# 08_B2B.net
KiCad netlist of a schematic drawn in Altium Designer
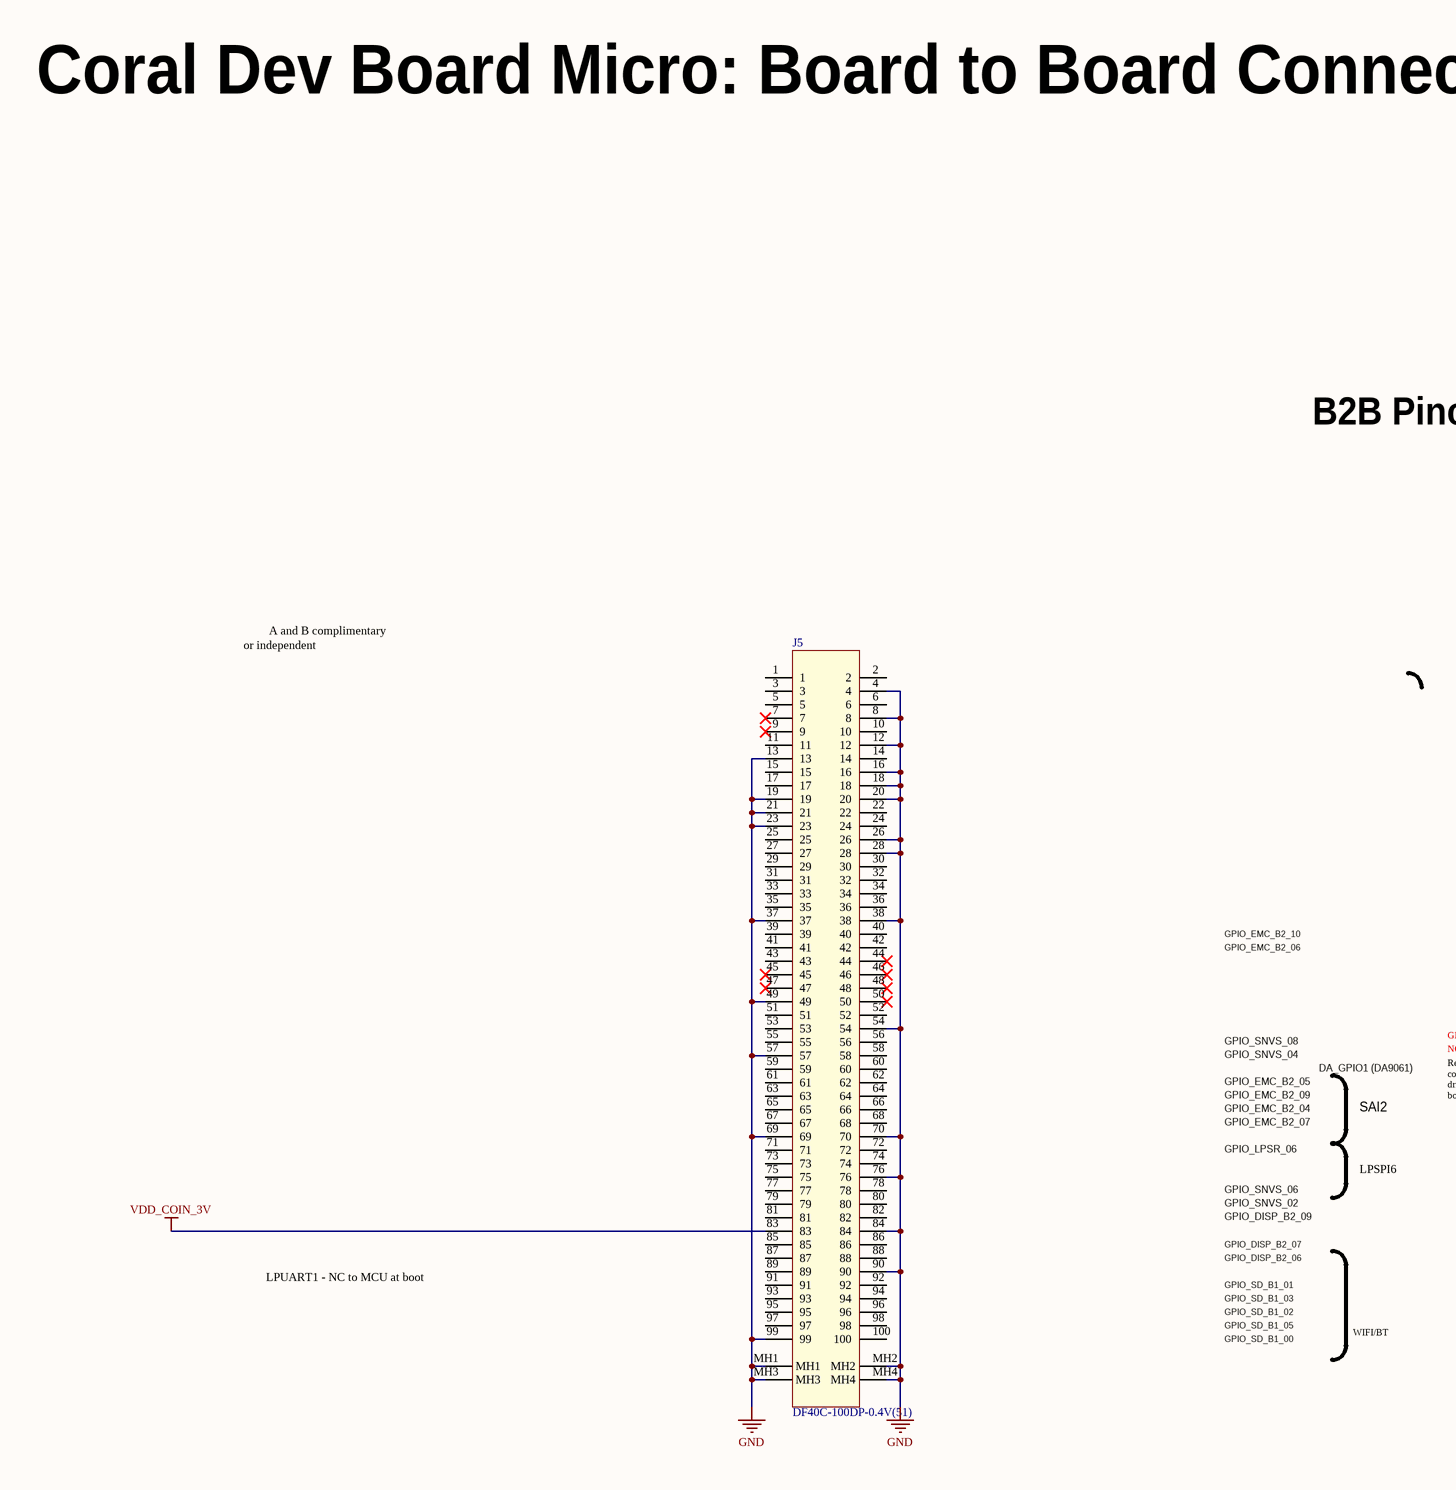
[diagram p0: 08 B2B.SchDoc, left]
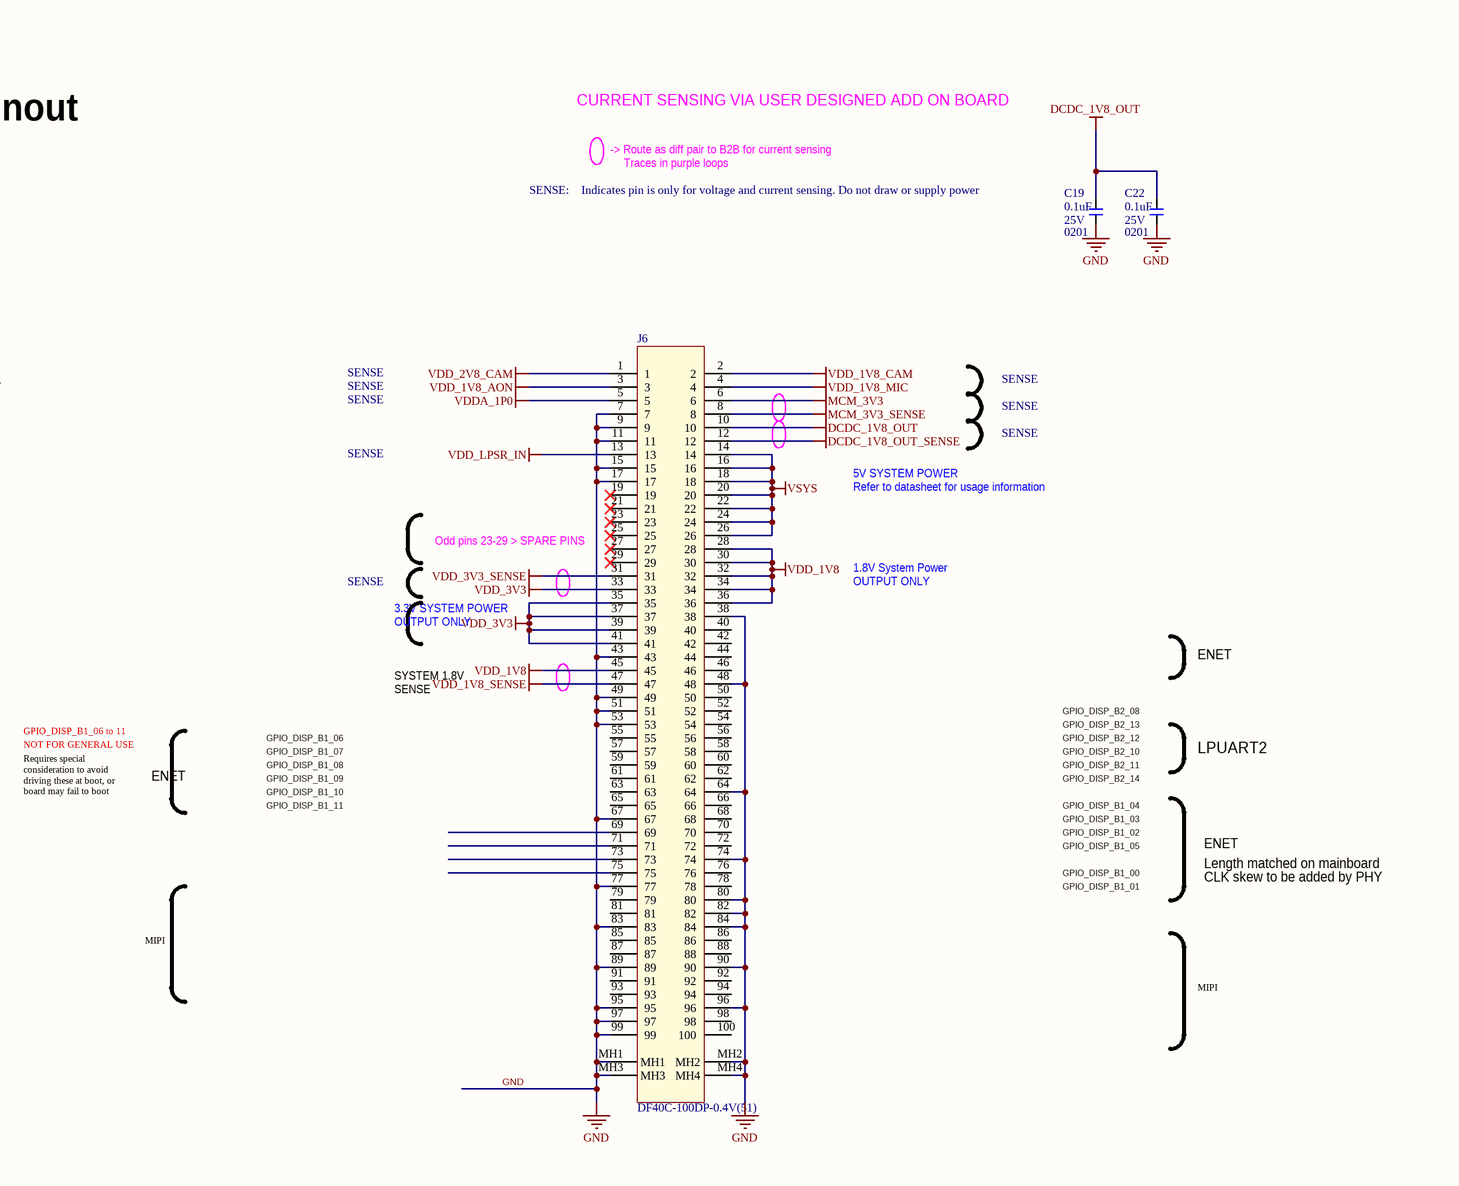
[diagram p1: 08 B2B.SchDoc, right]

(export (version "E")
  (design (tool "Eeschema 10.0.6"))
  (components
    (comp (ref "C19")
      (value "0.1uF")
      (footprint "C0201Y")
      (description "CAP, CER, X5R, 0.1uF, 25V, 20%, 0201, 0.33mm T")
      (fields
        (field (name "MFG") "MURATA")
        (field (name "PACKAGE") "0201")
        (field (name "VOLTAGE") "25V")
        (field (name "TOLERANCE") "20%")
      )
      (libsource (lib "AltiumReleaseLibDB") (part "__Template_Cap"))
    )
    (comp (ref "C22")
      (value "0.1uF")
      (footprint "C0201Y")
      (description "CAP, CER, X5R, 0.1uF, 25V, 20%, 0201, 0.33mm T")
      (fields
        (field (name "MFG") "MURATA")
        (field (name "PACKAGE") "0201")
        (field (name "VOLTAGE") "25V")
        (field (name "TOLERANCE") "20%")
      )
      (libsource (lib "AltiumReleaseLibDB") (part "__Template_Cap"))
    )
    (comp (ref "J5")
      (value "~")
      (footprint "HIROSE_DF40C-100DP-0.4V(51)")
      (description "CONN, HDR, VERT, 2x50, 0.4MM P, 1.14MM H, GOLD, SMD")
      (fields (field (name "MFG") "Hirose Electric Co Ltd") (field (name "MFG P/N") "DF40C-100DP-0.4V(51)"))
      (libsource (lib "AltiumReleaseLibDB") (part "__Template_Connector_2X50_4MH"))
    )
    (comp (ref "J6")
      (value "~")
      (footprint "HIROSE_DF40C-100DP-0.4V(51)")
      (description "CONN, HDR, VERT, 2x50, 0.4MM P, 1.14MM H, GOLD, SMD")
      (fields (field (name "MFG") "Hirose Electric Co Ltd") (field (name "MFG P/N") "DF40C-100DP-0.4V(51)"))
      (libsource (lib "AltiumReleaseLibDB") (part "__Template_Connector_2X50_4MH"))
    )
  )
  (nets
    (net (code "1") (name "DCDC_1V8_OUT") (class "Default")
      (node (ref "C19") (pin "1") (pintype "passive"))
      (node (ref "C22") (pin "1") (pintype "passive"))
      (node (ref "J6") (pin "10") (pinfunction "10_10") (pintype "passive"))
    )
    (net (code "2") (name "DCDC_1V8_OUT_SENSE") (class "Default")
      (node (ref "J6") (pin "12") (pinfunction "12_12") (pintype "passive"))
    )
    (net (code "3") (name "GND") (class "Default")
      (node (ref "C19") (pin "2") (pintype "passive"))
      (node (ref "C22") (pin "2") (pintype "passive"))
      (node (ref "J5") (pin "12") (pinfunction "12_12") (pintype "passive"))
      (node (ref "J5") (pin "13") (pinfunction "13_13") (pintype "passive"))
      (node (ref "J5") (pin "16") (pinfunction "16_16") (pintype "passive"))
      (node (ref "J5") (pin "18") (pinfunction "18_18") (pintype "passive"))
      (node (ref "J5") (pin "19") (pinfunction "19_19") (pintype "passive"))
      (node (ref "J5") (pin "20") (pinfunction "20_20") (pintype "passive"))
      (node (ref "J5") (pin "21") (pinfunction "21_21") (pintype "passive"))
      (node (ref "J5") (pin "23") (pinfunction "23_23") (pintype "passive"))
      (node (ref "J5") (pin "26") (pinfunction "26_26") (pintype "passive"))
      (node (ref "J5") (pin "28") (pinfunction "28_28") (pintype "passive"))
      (node (ref "J5") (pin "37") (pinfunction "37_37") (pintype "passive"))
      (node (ref "J5") (pin "38") (pinfunction "38_38") (pintype "passive"))
      (node (ref "J5") (pin "4") (pinfunction "4_4") (pintype "passive"))
      (node (ref "J5") (pin "49") (pinfunction "49_49") (pintype "passive"))
      (node (ref "J5") (pin "54") (pinfunction "54_54") (pintype "passive"))
      (node (ref "J5") (pin "57") (pinfunction "57_57") (pintype "passive"))
      (node (ref "J5") (pin "69") (pinfunction "69_69") (pintype "passive"))
      (node (ref "J5") (pin "70") (pinfunction "70_70") (pintype "passive"))
      (node (ref "J5") (pin "76") (pinfunction "76_76") (pintype "passive"))
      (node (ref "J5") (pin "8") (pinfunction "8_8") (pintype "passive"))
      (node (ref "J5") (pin "84") (pinfunction "84_84") (pintype "passive"))
      (node (ref "J5") (pin "90") (pinfunction "90_90") (pintype "passive"))
      (node (ref "J5") (pin "99") (pinfunction "99_99") (pintype "passive"))
      (node (ref "J5") (pin "MH1") (pinfunction "MH1_MH1") (pintype "passive"))
      (node (ref "J5") (pin "MH2") (pinfunction "MH2_MH2") (pintype "passive"))
      (node (ref "J5") (pin "MH3") (pinfunction "MH3_MH3") (pintype "passive"))
      (node (ref "J5") (pin "MH4") (pinfunction "MH4_MH4") (pintype "passive"))
      (node (ref "J6") (pin "11") (pinfunction "11_11") (pintype "passive"))
      (node (ref "J6") (pin "15") (pinfunction "15_15") (pintype "passive"))
      (node (ref "J6") (pin "17") (pinfunction "17_17") (pintype "passive"))
      (node (ref "J6") (pin "38") (pinfunction "38_38") (pintype "passive"))
      (node (ref "J6") (pin "43") (pinfunction "43_43") (pintype "passive"))
      (node (ref "J6") (pin "48") (pinfunction "48_48") (pintype "passive"))
      (node (ref "J6") (pin "49") (pinfunction "49_49") (pintype "passive"))
      (node (ref "J6") (pin "51") (pinfunction "51_51") (pintype "passive"))
      (node (ref "J6") (pin "53") (pinfunction "53_53") (pintype "passive"))
      (node (ref "J6") (pin "64") (pinfunction "64_64") (pintype "passive"))
      (node (ref "J6") (pin "67") (pinfunction "67_67") (pintype "passive"))
      (node (ref "J6") (pin "7") (pinfunction "7_7") (pintype "passive"))
      (node (ref "J6") (pin "74") (pinfunction "74_74") (pintype "passive"))
      (node (ref "J6") (pin "77") (pinfunction "77_77") (pintype "passive"))
      (node (ref "J6") (pin "80") (pinfunction "80_80") (pintype "passive"))
      (node (ref "J6") (pin "82") (pinfunction "82_82") (pintype "passive"))
      (node (ref "J6") (pin "83") (pinfunction "83_83") (pintype "passive"))
      (node (ref "J6") (pin "84") (pinfunction "84_84") (pintype "passive"))
      (node (ref "J6") (pin "89") (pinfunction "89_89") (pintype "passive"))
      (node (ref "J6") (pin "9") (pinfunction "9_9") (pintype "passive"))
      (node (ref "J6") (pin "90") (pinfunction "90_90") (pintype "passive"))
      (node (ref "J6") (pin "95") (pinfunction "95_95") (pintype "passive"))
      (node (ref "J6") (pin "96") (pinfunction "96_96") (pintype "passive"))
      (node (ref "J6") (pin "97") (pinfunction "97_97") (pintype "passive"))
      (node (ref "J6") (pin "99") (pinfunction "99_99") (pintype "passive"))
      (node (ref "J6") (pin "MH1") (pinfunction "MH1_MH1") (pintype "passive"))
      (node (ref "J6") (pin "MH2") (pinfunction "MH2_MH2") (pintype "passive"))
      (node (ref "J6") (pin "MH3") (pinfunction "MH3_MH3") (pintype "passive"))
      (node (ref "J6") (pin "MH4") (pinfunction "MH4_MH4") (pintype "passive"))
    )
    (net (code "4") (name "MCM_3V3") (class "Default")
      (node (ref "J6") (pin "6") (pinfunction "6_6") (pintype "passive"))
    )
    (net (code "5") (name "MCM_3V3_SENSE") (class "Default")
      (node (ref "J6") (pin "8") (pinfunction "8_8") (pintype "passive"))
    )
    (net (code "6") (name "VDDA_1P0") (class "Default")
      (node (ref "J6") (pin "5") (pinfunction "5_5") (pintype "passive"))
    )
    (net (code "7") (name "VDD_1V8") (class "Default")
      (node (ref "J6") (pin "28") (pinfunction "28_28") (pintype "passive"))
      (node (ref "J6") (pin "30") (pinfunction "30_30") (pintype "passive"))
      (node (ref "J6") (pin "32") (pinfunction "32_32") (pintype "passive"))
      (node (ref "J6") (pin "34") (pinfunction "34_34") (pintype "passive"))
      (node (ref "J6") (pin "36") (pinfunction "36_36") (pintype "passive"))
      (node (ref "J6") (pin "45") (pinfunction "45_45") (pintype "passive"))
    )
    (net (code "8") (name "VDD_1V8_AON") (class "Default")
      (node (ref "J6") (pin "3") (pinfunction "3_3") (pintype "passive"))
    )
    (net (code "9") (name "VDD_1V8_CAM") (class "Default")
      (node (ref "J6") (pin "2") (pinfunction "2_2") (pintype "passive"))
    )
    (net (code "10") (name "VDD_1V8_MIC") (class "Default")
      (node (ref "J6") (pin "4") (pinfunction "4_4") (pintype "passive"))
    )
    (net (code "11") (name "VDD_1V8_SENSE") (class "Default")
      (node (ref "J6") (pin "47") (pinfunction "47_47") (pintype "passive"))
    )
    (net (code "12") (name "VDD_2V8_CAM") (class "Default")
      (node (ref "J6") (pin "1") (pinfunction "1_1") (pintype "passive"))
    )
    (net (code "13") (name "VDD_3V3") (class "Default")
      (node (ref "J6") (pin "33") (pinfunction "33_33") (pintype "passive"))
      (node (ref "J6") (pin "35") (pinfunction "35_35") (pintype "passive"))
      (node (ref "J6") (pin "37") (pinfunction "37_37") (pintype "passive"))
      (node (ref "J6") (pin "39") (pinfunction "39_39") (pintype "passive"))
      (node (ref "J6") (pin "41") (pinfunction "41_41") (pintype "passive"))
    )
    (net (code "14") (name "VDD_3V3_SENSE") (class "Default")
      (node (ref "J6") (pin "31") (pinfunction "31_31") (pintype "passive"))
    )
    (net (code "15") (name "VDD_COIN_3V") (class "Default")
      (node (ref "J5") (pin "83") (pinfunction "83_83") (pintype "passive"))
    )
    (net (code "16") (name "VDD_LPSR_IN") (class "Default")
      (node (ref "J6") (pin "13") (pinfunction "13_13") (pintype "passive"))
    )
    (net (code "17") (name "VSYS") (class "Default")
      (node (ref "J6") (pin "14") (pinfunction "14_14") (pintype "passive"))
      (node (ref "J6") (pin "16") (pinfunction "16_16") (pintype "passive"))
      (node (ref "J6") (pin "18") (pinfunction "18_18") (pintype "passive"))
      (node (ref "J6") (pin "20") (pinfunction "20_20") (pintype "passive"))
      (node (ref "J6") (pin "22") (pinfunction "22_22") (pintype "passive"))
      (node (ref "J6") (pin "24") (pinfunction "24_24") (pintype "passive"))
      (node (ref "J6") (pin "26") (pinfunction "26_26") (pintype "passive"))
    )
    (net (code "18") (name "unconnected-(J5-Pad1)") (class "Default")
      (node (ref "J5") (pin "1") (pinfunction "1_1") (pintype "passive"))
    )
    (net (code "19") (name "unconnected-(J5-Pad2)") (class "Default")
      (node (ref "J5") (pin "2") (pinfunction "2_2") (pintype "passive"))
    )
    (net (code "20") (name "unconnected-(J5-Pad3)") (class "Default")
      (node (ref "J5") (pin "3") (pinfunction "3_3") (pintype "passive"))
    )
    (net (code "21") (name "unconnected-(J5-Pad5)") (class "Default")
      (node (ref "J5") (pin "5") (pinfunction "5_5") (pintype "passive"))
    )
    (net (code "22") (name "unconnected-(J5-Pad6)") (class "Default")
      (node (ref "J5") (pin "6") (pinfunction "6_6") (pintype "passive"))
    )
    (net (code "23") (name "unconnected-(J5-Pad7)") (class "Default")
      (node (ref "J5") (pin "7") (pinfunction "7_7") (pintype "passive+no_connect"))
    )
    (net (code "24") (name "unconnected-(J5-Pad9)") (class "Default")
      (node (ref "J5") (pin "9") (pinfunction "9_9") (pintype "passive+no_connect"))
    )
    (net (code "25") (name "unconnected-(J5-Pad10)") (class "Default")
      (node (ref "J5") (pin "10") (pinfunction "10_10") (pintype "passive"))
    )
    (net (code "26") (name "unconnected-(J5-Pad11)") (class "Default")
      (node (ref "J5") (pin "11") (pinfunction "11_11") (pintype "passive"))
    )
    (net (code "27") (name "unconnected-(J5-Pad14)") (class "Default")
      (node (ref "J5") (pin "14") (pinfunction "14_14") (pintype "passive"))
    )
    (net (code "28") (name "unconnected-(J5-Pad15)") (class "Default")
      (node (ref "J5") (pin "15") (pinfunction "15_15") (pintype "passive"))
    )
    (net (code "29") (name "unconnected-(J5-Pad17)") (class "Default")
      (node (ref "J5") (pin "17") (pinfunction "17_17") (pintype "passive"))
    )
    (net (code "30") (name "unconnected-(J5-Pad22)") (class "Default")
      (node (ref "J5") (pin "22") (pinfunction "22_22") (pintype "passive"))
    )
    (net (code "31") (name "unconnected-(J5-Pad24)") (class "Default")
      (node (ref "J5") (pin "24") (pinfunction "24_24") (pintype "passive"))
    )
    (net (code "32") (name "unconnected-(J5-Pad25)") (class "Default")
      (node (ref "J5") (pin "25") (pinfunction "25_25") (pintype "passive"))
    )
    (net (code "33") (name "unconnected-(J5-Pad27)") (class "Default")
      (node (ref "J5") (pin "27") (pinfunction "27_27") (pintype "passive"))
    )
    (net (code "34") (name "unconnected-(J5-Pad29)") (class "Default")
      (node (ref "J5") (pin "29") (pinfunction "29_29") (pintype "passive"))
    )
    (net (code "35") (name "unconnected-(J5-Pad30)") (class "Default")
      (node (ref "J5") (pin "30") (pinfunction "30_30") (pintype "passive"))
    )
    (net (code "36") (name "unconnected-(J5-Pad31)") (class "Default")
      (node (ref "J5") (pin "31") (pinfunction "31_31") (pintype "passive"))
    )
    (net (code "37") (name "unconnected-(J5-Pad32)") (class "Default")
      (node (ref "J5") (pin "32") (pinfunction "32_32") (pintype "passive"))
    )
    (net (code "38") (name "unconnected-(J5-Pad33)") (class "Default")
      (node (ref "J5") (pin "33") (pinfunction "33_33") (pintype "passive"))
    )
    (net (code "39") (name "unconnected-(J5-Pad34)") (class "Default")
      (node (ref "J5") (pin "34") (pinfunction "34_34") (pintype "passive"))
    )
    (net (code "40") (name "unconnected-(J5-Pad35)") (class "Default")
      (node (ref "J5") (pin "35") (pinfunction "35_35") (pintype "passive"))
    )
    (net (code "41") (name "unconnected-(J5-Pad36)") (class "Default")
      (node (ref "J5") (pin "36") (pinfunction "36_36") (pintype "passive"))
    )
    (net (code "42") (name "unconnected-(J5-Pad39)") (class "Default")
      (node (ref "J5") (pin "39") (pinfunction "39_39") (pintype "passive"))
    )
    (net (code "43") (name "unconnected-(J5-Pad40)") (class "Default")
      (node (ref "J5") (pin "40") (pinfunction "40_40") (pintype "passive"))
    )
    (net (code "44") (name "unconnected-(J5-Pad41)") (class "Default")
      (node (ref "J5") (pin "41") (pinfunction "41_41") (pintype "passive"))
    )
    (net (code "45") (name "unconnected-(J5-Pad42)") (class "Default")
      (node (ref "J5") (pin "42") (pinfunction "42_42") (pintype "passive"))
    )
    (net (code "46") (name "unconnected-(J5-Pad43)") (class "Default")
      (node (ref "J5") (pin "43") (pinfunction "43_43") (pintype "passive"))
    )
    (net (code "47") (name "unconnected-(J5-Pad44)") (class "Default")
      (node (ref "J5") (pin "44") (pinfunction "44_44") (pintype "passive+no_connect"))
    )
    (net (code "48") (name "unconnected-(J5-Pad45)") (class "Default")
      (node (ref "J5") (pin "45") (pinfunction "45_45") (pintype "passive+no_connect"))
    )
    (net (code "49") (name "unconnected-(J5-Pad46)") (class "Default")
      (node (ref "J5") (pin "46") (pinfunction "46_46") (pintype "passive+no_connect"))
    )
    (net (code "50") (name "unconnected-(J5-Pad47)") (class "Default")
      (node (ref "J5") (pin "47") (pinfunction "47_47") (pintype "passive+no_connect"))
    )
    (net (code "51") (name "unconnected-(J5-Pad48)") (class "Default")
      (node (ref "J5") (pin "48") (pinfunction "48_48") (pintype "passive+no_connect"))
    )
    (net (code "52") (name "unconnected-(J5-Pad50)") (class "Default")
      (node (ref "J5") (pin "50") (pinfunction "50_50") (pintype "passive+no_connect"))
    )
    (net (code "53") (name "unconnected-(J5-Pad51)") (class "Default")
      (node (ref "J5") (pin "51") (pinfunction "51_51") (pintype "passive"))
    )
    (net (code "54") (name "unconnected-(J5-Pad52)") (class "Default")
      (node (ref "J5") (pin "52") (pinfunction "52_52") (pintype "passive"))
    )
    (net (code "55") (name "unconnected-(J5-Pad53)") (class "Default")
      (node (ref "J5") (pin "53") (pinfunction "53_53") (pintype "passive"))
    )
    (net (code "56") (name "unconnected-(J5-Pad55)") (class "Default")
      (node (ref "J5") (pin "55") (pinfunction "55_55") (pintype "passive"))
    )
    (net (code "57") (name "unconnected-(J5-Pad56)") (class "Default")
      (node (ref "J5") (pin "56") (pinfunction "56_56") (pintype "passive"))
    )
    (net (code "58") (name "unconnected-(J5-Pad58)") (class "Default")
      (node (ref "J5") (pin "58") (pinfunction "58_58") (pintype "passive"))
    )
    (net (code "59") (name "unconnected-(J5-Pad59)") (class "Default")
      (node (ref "J5") (pin "59") (pinfunction "59_59") (pintype "passive"))
    )
    (net (code "60") (name "unconnected-(J5-Pad60)") (class "Default")
      (node (ref "J5") (pin "60") (pinfunction "60_60") (pintype "passive"))
    )
    (net (code "61") (name "unconnected-(J5-Pad61)") (class "Default")
      (node (ref "J5") (pin "61") (pinfunction "61_61") (pintype "passive"))
    )
    (net (code "62") (name "unconnected-(J5-Pad62)") (class "Default")
      (node (ref "J5") (pin "62") (pinfunction "62_62") (pintype "passive"))
    )
    (net (code "63") (name "unconnected-(J5-Pad63)") (class "Default")
      (node (ref "J5") (pin "63") (pinfunction "63_63") (pintype "passive"))
    )
    (net (code "64") (name "unconnected-(J5-Pad64)") (class "Default")
      (node (ref "J5") (pin "64") (pinfunction "64_64") (pintype "passive"))
    )
    (net (code "65") (name "unconnected-(J5-Pad65)") (class "Default")
      (node (ref "J5") (pin "65") (pinfunction "65_65") (pintype "passive"))
    )
    (net (code "66") (name "unconnected-(J5-Pad66)") (class "Default")
      (node (ref "J5") (pin "66") (pinfunction "66_66") (pintype "passive"))
    )
    (net (code "67") (name "unconnected-(J5-Pad67)") (class "Default")
      (node (ref "J5") (pin "67") (pinfunction "67_67") (pintype "passive"))
    )
    (net (code "68") (name "unconnected-(J5-Pad68)") (class "Default")
      (node (ref "J5") (pin "68") (pinfunction "68_68") (pintype "passive"))
    )
    (net (code "69") (name "unconnected-(J5-Pad71)") (class "Default")
      (node (ref "J5") (pin "71") (pinfunction "71_71") (pintype "passive"))
    )
    (net (code "70") (name "unconnected-(J5-Pad72)") (class "Default")
      (node (ref "J5") (pin "72") (pinfunction "72_72") (pintype "passive"))
    )
    (net (code "71") (name "unconnected-(J5-Pad73)") (class "Default")
      (node (ref "J5") (pin "73") (pinfunction "73_73") (pintype "passive"))
    )
    (net (code "72") (name "unconnected-(J5-Pad74)") (class "Default")
      (node (ref "J5") (pin "74") (pinfunction "74_74") (pintype "passive"))
    )
    (net (code "73") (name "unconnected-(J5-Pad75)") (class "Default")
      (node (ref "J5") (pin "75") (pinfunction "75_75") (pintype "passive"))
    )
    (net (code "74") (name "unconnected-(J5-Pad77)") (class "Default")
      (node (ref "J5") (pin "77") (pinfunction "77_77") (pintype "passive"))
    )
    (net (code "75") (name "unconnected-(J5-Pad78)") (class "Default")
      (node (ref "J5") (pin "78") (pinfunction "78_78") (pintype "passive"))
    )
    (net (code "76") (name "unconnected-(J5-Pad79)") (class "Default")
      (node (ref "J5") (pin "79") (pinfunction "79_79") (pintype "passive"))
    )
    (net (code "77") (name "unconnected-(J5-Pad80)") (class "Default")
      (node (ref "J5") (pin "80") (pinfunction "80_80") (pintype "passive"))
    )
    (net (code "78") (name "unconnected-(J5-Pad81)") (class "Default")
      (node (ref "J5") (pin "81") (pinfunction "81_81") (pintype "passive"))
    )
    (net (code "79") (name "unconnected-(J5-Pad82)") (class "Default")
      (node (ref "J5") (pin "82") (pinfunction "82_82") (pintype "passive"))
    )
    (net (code "80") (name "unconnected-(J5-Pad85)") (class "Default")
      (node (ref "J5") (pin "85") (pinfunction "85_85") (pintype "passive"))
    )
    (net (code "81") (name "unconnected-(J5-Pad86)") (class "Default")
      (node (ref "J5") (pin "86") (pinfunction "86_86") (pintype "passive"))
    )
    (net (code "82") (name "unconnected-(J5-Pad87)") (class "Default")
      (node (ref "J5") (pin "87") (pinfunction "87_87") (pintype "passive"))
    )
    (net (code "83") (name "unconnected-(J5-Pad88)") (class "Default")
      (node (ref "J5") (pin "88") (pinfunction "88_88") (pintype "passive"))
    )
    (net (code "84") (name "unconnected-(J5-Pad89)") (class "Default")
      (node (ref "J5") (pin "89") (pinfunction "89_89") (pintype "passive"))
    )
    (net (code "85") (name "unconnected-(J5-Pad91)") (class "Default")
      (node (ref "J5") (pin "91") (pinfunction "91_91") (pintype "passive"))
    )
    (net (code "86") (name "unconnected-(J5-Pad92)") (class "Default")
      (node (ref "J5") (pin "92") (pinfunction "92_92") (pintype "passive"))
    )
    (net (code "87") (name "unconnected-(J5-Pad93)") (class "Default")
      (node (ref "J5") (pin "93") (pinfunction "93_93") (pintype "passive"))
    )
    (net (code "88") (name "unconnected-(J5-Pad94)") (class "Default")
      (node (ref "J5") (pin "94") (pinfunction "94_94") (pintype "passive"))
    )
    (net (code "89") (name "unconnected-(J5-Pad95)") (class "Default")
      (node (ref "J5") (pin "95") (pinfunction "95_95") (pintype "passive"))
    )
    (net (code "90") (name "unconnected-(J5-Pad96)") (class "Default")
      (node (ref "J5") (pin "96") (pinfunction "96_96") (pintype "passive"))
    )
    (net (code "91") (name "unconnected-(J5-Pad97)") (class "Default")
      (node (ref "J5") (pin "97") (pinfunction "97_97") (pintype "passive"))
    )
    (net (code "92") (name "unconnected-(J5-Pad98)") (class "Default")
      (node (ref "J5") (pin "98") (pinfunction "98_98") (pintype "passive"))
    )
    (net (code "93") (name "unconnected-(J5-Pad100)") (class "Default")
      (node (ref "J5") (pin "100") (pinfunction "100_100") (pintype "passive"))
    )
    (net (code "94") (name "unconnected-(J6-Pad19)") (class "Default")
      (node (ref "J6") (pin "19") (pinfunction "19_19") (pintype "passive+no_connect"))
    )
    (net (code "95") (name "unconnected-(J6-Pad21)") (class "Default")
      (node (ref "J6") (pin "21") (pinfunction "21_21") (pintype "passive+no_connect"))
    )
    (net (code "96") (name "unconnected-(J6-Pad23)") (class "Default")
      (node (ref "J6") (pin "23") (pinfunction "23_23") (pintype "passive+no_connect"))
    )
    (net (code "97") (name "unconnected-(J6-Pad25)") (class "Default")
      (node (ref "J6") (pin "25") (pinfunction "25_25") (pintype "passive+no_connect"))
    )
    (net (code "98") (name "unconnected-(J6-Pad27)") (class "Default")
      (node (ref "J6") (pin "27") (pinfunction "27_27") (pintype "passive+no_connect"))
    )
    (net (code "99") (name "unconnected-(J6-Pad29)") (class "Default")
      (node (ref "J6") (pin "29") (pinfunction "29_29") (pintype "passive+no_connect"))
    )
    (net (code "100") (name "unconnected-(J6-Pad40)") (class "Default")
      (node (ref "J6") (pin "40") (pinfunction "40_40") (pintype "passive"))
    )
    (net (code "101") (name "unconnected-(J6-Pad42)") (class "Default")
      (node (ref "J6") (pin "42") (pinfunction "42_42") (pintype "passive"))
    )
    (net (code "102") (name "unconnected-(J6-Pad44)") (class "Default")
      (node (ref "J6") (pin "44") (pinfunction "44_44") (pintype "passive"))
    )
    (net (code "103") (name "unconnected-(J6-Pad46)") (class "Default")
      (node (ref "J6") (pin "46") (pinfunction "46_46") (pintype "passive"))
    )
    (net (code "104") (name "unconnected-(J6-Pad50)") (class "Default")
      (node (ref "J6") (pin "50") (pinfunction "50_50") (pintype "passive"))
    )
    (net (code "105") (name "unconnected-(J6-Pad52)") (class "Default")
      (node (ref "J6") (pin "52") (pinfunction "52_52") (pintype "passive"))
    )
    (net (code "106") (name "unconnected-(J6-Pad54)") (class "Default")
      (node (ref "J6") (pin "54") (pinfunction "54_54") (pintype "passive"))
    )
    (net (code "107") (name "unconnected-(J6-Pad55)") (class "Default")
      (node (ref "J6") (pin "55") (pinfunction "55_55") (pintype "passive"))
    )
    (net (code "108") (name "unconnected-(J6-Pad56)") (class "Default")
      (node (ref "J6") (pin "56") (pinfunction "56_56") (pintype "passive"))
    )
    (net (code "109") (name "unconnected-(J6-Pad57)") (class "Default")
      (node (ref "J6") (pin "57") (pinfunction "57_57") (pintype "passive"))
    )
    (net (code "110") (name "unconnected-(J6-Pad58)") (class "Default")
      (node (ref "J6") (pin "58") (pinfunction "58_58") (pintype "passive"))
    )
    (net (code "111") (name "unconnected-(J6-Pad59)") (class "Default")
      (node (ref "J6") (pin "59") (pinfunction "59_59") (pintype "passive"))
    )
    (net (code "112") (name "unconnected-(J6-Pad60)") (class "Default")
      (node (ref "J6") (pin "60") (pinfunction "60_60") (pintype "passive"))
    )
    (net (code "113") (name "unconnected-(J6-Pad61)") (class "Default")
      (node (ref "J6") (pin "61") (pinfunction "61_61") (pintype "passive"))
    )
    (net (code "114") (name "unconnected-(J6-Pad62)") (class "Default")
      (node (ref "J6") (pin "62") (pinfunction "62_62") (pintype "passive"))
    )
    (net (code "115") (name "unconnected-(J6-Pad63)") (class "Default")
      (node (ref "J6") (pin "63") (pinfunction "63_63") (pintype "passive"))
    )
    (net (code "116") (name "unconnected-(J6-Pad65)") (class "Default")
      (node (ref "J6") (pin "65") (pinfunction "65_65") (pintype "passive"))
    )
    (net (code "117") (name "unconnected-(J6-Pad66)") (class "Default")
      (node (ref "J6") (pin "66") (pinfunction "66_66") (pintype "passive"))
    )
    (net (code "118") (name "unconnected-(J6-Pad68)") (class "Default")
      (node (ref "J6") (pin "68") (pinfunction "68_68") (pintype "passive"))
    )
    (net (code "119") (name "unconnected-(J6-Pad69)") (class "Default")
      (node (ref "J6") (pin "69") (pinfunction "69_69") (pintype "passive"))
    )
    (net (code "120") (name "unconnected-(J6-Pad70)") (class "Default")
      (node (ref "J6") (pin "70") (pinfunction "70_70") (pintype "passive"))
    )
    (net (code "121") (name "unconnected-(J6-Pad71)") (class "Default")
      (node (ref "J6") (pin "71") (pinfunction "71_71") (pintype "passive"))
    )
    (net (code "122") (name "unconnected-(J6-Pad72)") (class "Default")
      (node (ref "J6") (pin "72") (pinfunction "72_72") (pintype "passive"))
    )
    (net (code "123") (name "unconnected-(J6-Pad73)") (class "Default")
      (node (ref "J6") (pin "73") (pinfunction "73_73") (pintype "passive"))
    )
    (net (code "124") (name "unconnected-(J6-Pad75)") (class "Default")
      (node (ref "J6") (pin "75") (pinfunction "75_75") (pintype "passive"))
    )
    (net (code "125") (name "unconnected-(J6-Pad76)") (class "Default")
      (node (ref "J6") (pin "76") (pinfunction "76_76") (pintype "passive"))
    )
    (net (code "126") (name "unconnected-(J6-Pad78)") (class "Default")
      (node (ref "J6") (pin "78") (pinfunction "78_78") (pintype "passive"))
    )
    (net (code "127") (name "unconnected-(J6-Pad79)") (class "Default")
      (node (ref "J6") (pin "79") (pinfunction "79_79") (pintype "passive"))
    )
    (net (code "128") (name "unconnected-(J6-Pad81)") (class "Default")
      (node (ref "J6") (pin "81") (pinfunction "81_81") (pintype "passive"))
    )
    (net (code "129") (name "unconnected-(J6-Pad85)") (class "Default")
      (node (ref "J6") (pin "85") (pinfunction "85_85") (pintype "passive"))
    )
    (net (code "130") (name "unconnected-(J6-Pad86)") (class "Default")
      (node (ref "J6") (pin "86") (pinfunction "86_86") (pintype "passive"))
    )
    (net (code "131") (name "unconnected-(J6-Pad87)") (class "Default")
      (node (ref "J6") (pin "87") (pinfunction "87_87") (pintype "passive"))
    )
    (net (code "132") (name "unconnected-(J6-Pad88)") (class "Default")
      (node (ref "J6") (pin "88") (pinfunction "88_88") (pintype "passive"))
    )
    (net (code "133") (name "unconnected-(J6-Pad91)") (class "Default")
      (node (ref "J6") (pin "91") (pinfunction "91_91") (pintype "passive"))
    )
    (net (code "134") (name "unconnected-(J6-Pad92)") (class "Default")
      (node (ref "J6") (pin "92") (pinfunction "92_92") (pintype "passive"))
    )
    (net (code "135") (name "unconnected-(J6-Pad93)") (class "Default")
      (node (ref "J6") (pin "93") (pinfunction "93_93") (pintype "passive"))
    )
    (net (code "136") (name "unconnected-(J6-Pad94)") (class "Default")
      (node (ref "J6") (pin "94") (pinfunction "94_94") (pintype "passive"))
    )
    (net (code "137") (name "unconnected-(J6-Pad98)") (class "Default")
      (node (ref "J6") (pin "98") (pinfunction "98_98") (pintype "passive"))
    )
    (net (code "138") (name "unconnected-(J6-Pad100)") (class "Default")
      (node (ref "J6") (pin "100") (pinfunction "100_100") (pintype "passive"))
    )
  )
)
